# input_module.net
KiCad netlist of a schematic drawn in EAGLE
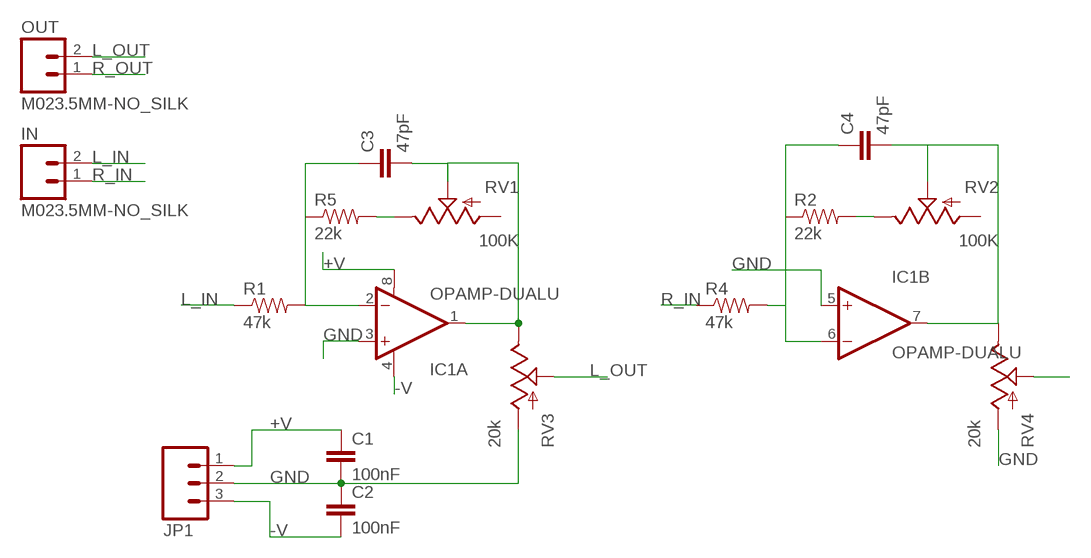
[diagram p0: schematic, sheet 1]

(export (version "E")
  (design (tool "Eeschema 10.0.6"))
  (components
    (comp (ref "C1")
      (value "100nF")
      (footprint "eagle-import:1206")
      (libsource (lib "eagle-import") (part "CAP1206"))
    )
    (comp (ref "C2")
      (value "100nF")
      (footprint "eagle-import:1206")
      (libsource (lib "eagle-import") (part "CAP1206"))
    )
    (comp (ref "C3")
      (value "47pF")
      (footprint "eagle-import:0805")
      (libsource (lib "eagle-import") (part "SparkFun-Passives_CAP0805"))
    )
    (comp (ref "C4")
      (value "47pF")
      (footprint "eagle-import:0805")
      (libsource (lib "eagle-import") (part "SparkFun-Passives_CAP0805"))
    )
    (comp (ref "IC1")
      (value "OPAMP-DUALU")
      (footprint "eagle-import:SO08")
      (libsource (lib "eagle-import") (part "OPAMP-DUALU"))
    )
    (comp (ref "IN")
      (value "M023.5MM-NO_SILK")
      (footprint "eagle-import:SCREWTERMINAL-3.5MM-2-NS")
      (libsource (lib "eagle-import") (part "M023.5MM-NO_SILK"))
    )
    (comp (ref "JP1")
      (value "M03SCREW")
      (footprint "eagle-import:SCREWTERMINAL-3.5MM-3")
      (libsource (lib "eagle-import") (part "M03SCREW"))
    )
    (comp (ref "OUT")
      (value "M023.5MM-NO_SILK")
      (footprint "eagle-import:SCREWTERMINAL-3.5MM-2-NS")
      (libsource (lib "eagle-import") (part "M023.5MM-NO_SILK"))
    )
    (comp (ref "R1")
      (value "47k")
      (footprint "eagle-import:AXIAL-0.4")
      (libsource (lib "eagle-import") (part "RESISTORPTH-1/4W"))
    )
    (comp (ref "R2")
      (value "22k")
      (footprint "eagle-import:AXIAL-0.4")
      (libsource (lib "eagle-import") (part "RESISTORPTH-1/4W"))
    )
    (comp (ref "R4")
      (value "47k")
      (footprint "eagle-import:AXIAL-0.4")
      (libsource (lib "eagle-import") (part "RESISTORPTH-1/4W"))
    )
    (comp (ref "R5")
      (value "22k")
      (footprint "eagle-import:AXIAL-0.4")
      (libsource (lib "eagle-import") (part "RESISTORPTH-1/4W"))
    )
    (comp (ref "RV1")
      (value "100K")
      (footprint "eagle-import:TRIM_POT")
      (libsource (lib "eagle-import") (part "POTTRIM"))
    )
    (comp (ref "RV2")
      (value "100K")
      (footprint "eagle-import:TRIM_POT")
      (libsource (lib "eagle-import") (part "POTTRIM"))
    )
    (comp (ref "RV3")
      (value "20k")
      (footprint "eagle-import:ALPS_POT")
      (libsource (lib "eagle-import") (part "POT"))
    )
    (comp (ref "RV4")
      (value "20k")
      (footprint "eagle-import:ALPS_POT")
      (libsource (lib "eagle-import") (part "POT"))
    )
  )
  (nets
    (net (code "1") (name "/+V") (class "Default")
      (node (ref "C1") (pin "1") (pinfunction "1_1") (pintype "passive"))
      (node (ref "IC1") (pin "8") (pinfunction "V+_8") (pintype "power_in"))
      (node (ref "JP1") (pin "1") (pinfunction "1_1") (pintype "passive"))
    )
    (net (code "2") (name "/-V") (class "Default")
      (node (ref "C2") (pin "2") (pinfunction "2_2") (pintype "passive"))
      (node (ref "IC1") (pin "4") (pinfunction "V-_4") (pintype "power_in"))
      (node (ref "JP1") (pin "3") (pinfunction "3_3") (pintype "passive"))
    )
    (net (code "3") (name "/GND") (class "Default")
      (node (ref "C1") (pin "2") (pinfunction "2_2") (pintype "passive"))
      (node (ref "C2") (pin "1") (pinfunction "1_1") (pintype "passive"))
      (node (ref "IC1") (pin "3") (pinfunction "+IN_3") (pintype "input"))
      (node (ref "IC1") (pin "5") (pinfunction "+IN_5") (pintype "input"))
      (node (ref "JP1") (pin "2") (pinfunction "2_2") (pintype "passive"))
      (node (ref "RV3") (pin "P$3") (pinfunction "A_P$3") (pintype "passive"))
      (node (ref "RV4") (pin "P$3") (pinfunction "A_P$3") (pintype "passive"))
    )
    (net (code "4") (name "/L_IN") (class "Default")
      (node (ref "IN") (pin "2") (pinfunction "2_2") (pintype "passive"))
      (node (ref "R1") (pin "P$1") (pinfunction "1_P$1") (pintype "passive"))
    )
    (net (code "5") (name "/L_OUT") (class "Default")
      (node (ref "OUT") (pin "2") (pinfunction "2_2") (pintype "passive"))
      (node (ref "RV3") (pin "P$2") (pinfunction "S_P$2") (pintype "passive"))
    )
    (net (code "6") (name "/R_IN") (class "Default")
      (node (ref "IN") (pin "1") (pinfunction "1_1") (pintype "passive"))
      (node (ref "R4") (pin "P$1") (pinfunction "1_P$1") (pintype "passive"))
    )
    (net (code "7") (name "/R_OUT") (class "Default")
      (node (ref "OUT") (pin "1") (pinfunction "1_1") (pintype "passive"))
      (node (ref "RV4") (pin "P$2") (pinfunction "S_P$2") (pintype "passive"))
    )
    (net (code "8") (name "Net-(IC1A--IN)") (class "Default")
      (node (ref "C3") (pin "1") (pinfunction "1_1") (pintype "passive"))
      (node (ref "IC1") (pin "2") (pinfunction "-IN_2") (pintype "input"))
      (node (ref "R1") (pin "P$2") (pinfunction "2_P$2") (pintype "passive"))
      (node (ref "R5") (pin "P$1") (pinfunction "1_P$1") (pintype "passive"))
    )
    (net (code "9") (name "Net-(IC1A-OUT)") (class "Default")
      (node (ref "C3") (pin "2") (pinfunction "2_2") (pintype "passive"))
      (node (ref "IC1") (pin "1") (pinfunction "OUT_1") (pintype "output"))
      (node (ref "RV1") (pin "1") (pinfunction "S_1") (pintype "passive"))
      (node (ref "RV3") (pin "P$1") (pinfunction "E_P$1") (pintype "passive"))
    )
    (net (code "10") (name "Net-(IC1B--IN)") (class "Default")
      (node (ref "C4") (pin "1") (pinfunction "1_1") (pintype "passive"))
      (node (ref "IC1") (pin "6") (pinfunction "-IN_6") (pintype "input"))
      (node (ref "R2") (pin "P$1") (pinfunction "1_P$1") (pintype "passive"))
      (node (ref "R4") (pin "P$2") (pinfunction "2_P$2") (pintype "passive"))
    )
    (net (code "11") (name "Net-(IC1B-OUT)") (class "Default")
      (node (ref "C4") (pin "2") (pinfunction "2_2") (pintype "passive"))
      (node (ref "IC1") (pin "7") (pinfunction "OUT_7") (pintype "output"))
      (node (ref "RV2") (pin "1") (pinfunction "S_1") (pintype "passive"))
      (node (ref "RV4") (pin "P$1") (pinfunction "E_P$1") (pintype "passive"))
    )
    (net (code "12") (name "Net-(R2-2)") (class "Default")
      (node (ref "R2") (pin "P$2") (pinfunction "2_P$2") (pintype "passive"))
      (node (ref "RV2") (pin "2") (pinfunction "E_2") (pintype "passive"))
    )
    (net (code "13") (name "Net-(R5-2)") (class "Default")
      (node (ref "R5") (pin "P$2") (pinfunction "2_P$2") (pintype "passive"))
      (node (ref "RV1") (pin "2") (pinfunction "E_2") (pintype "passive"))
    )
    (net (code "14") (name "unconnected-(RV1-A-Pad3)") (class "Default")
      (node (ref "RV1") (pin "3") (pinfunction "A_3") (pintype "passive"))
    )
    (net (code "15") (name "unconnected-(RV2-A-Pad3)") (class "Default")
      (node (ref "RV2") (pin "3") (pinfunction "A_3") (pintype "passive"))
    )
  )
)
